# SCH_Ribery_MotherBoard_2024-03-02.net
KiCad netlist of a schematic drawn in EasyEDA
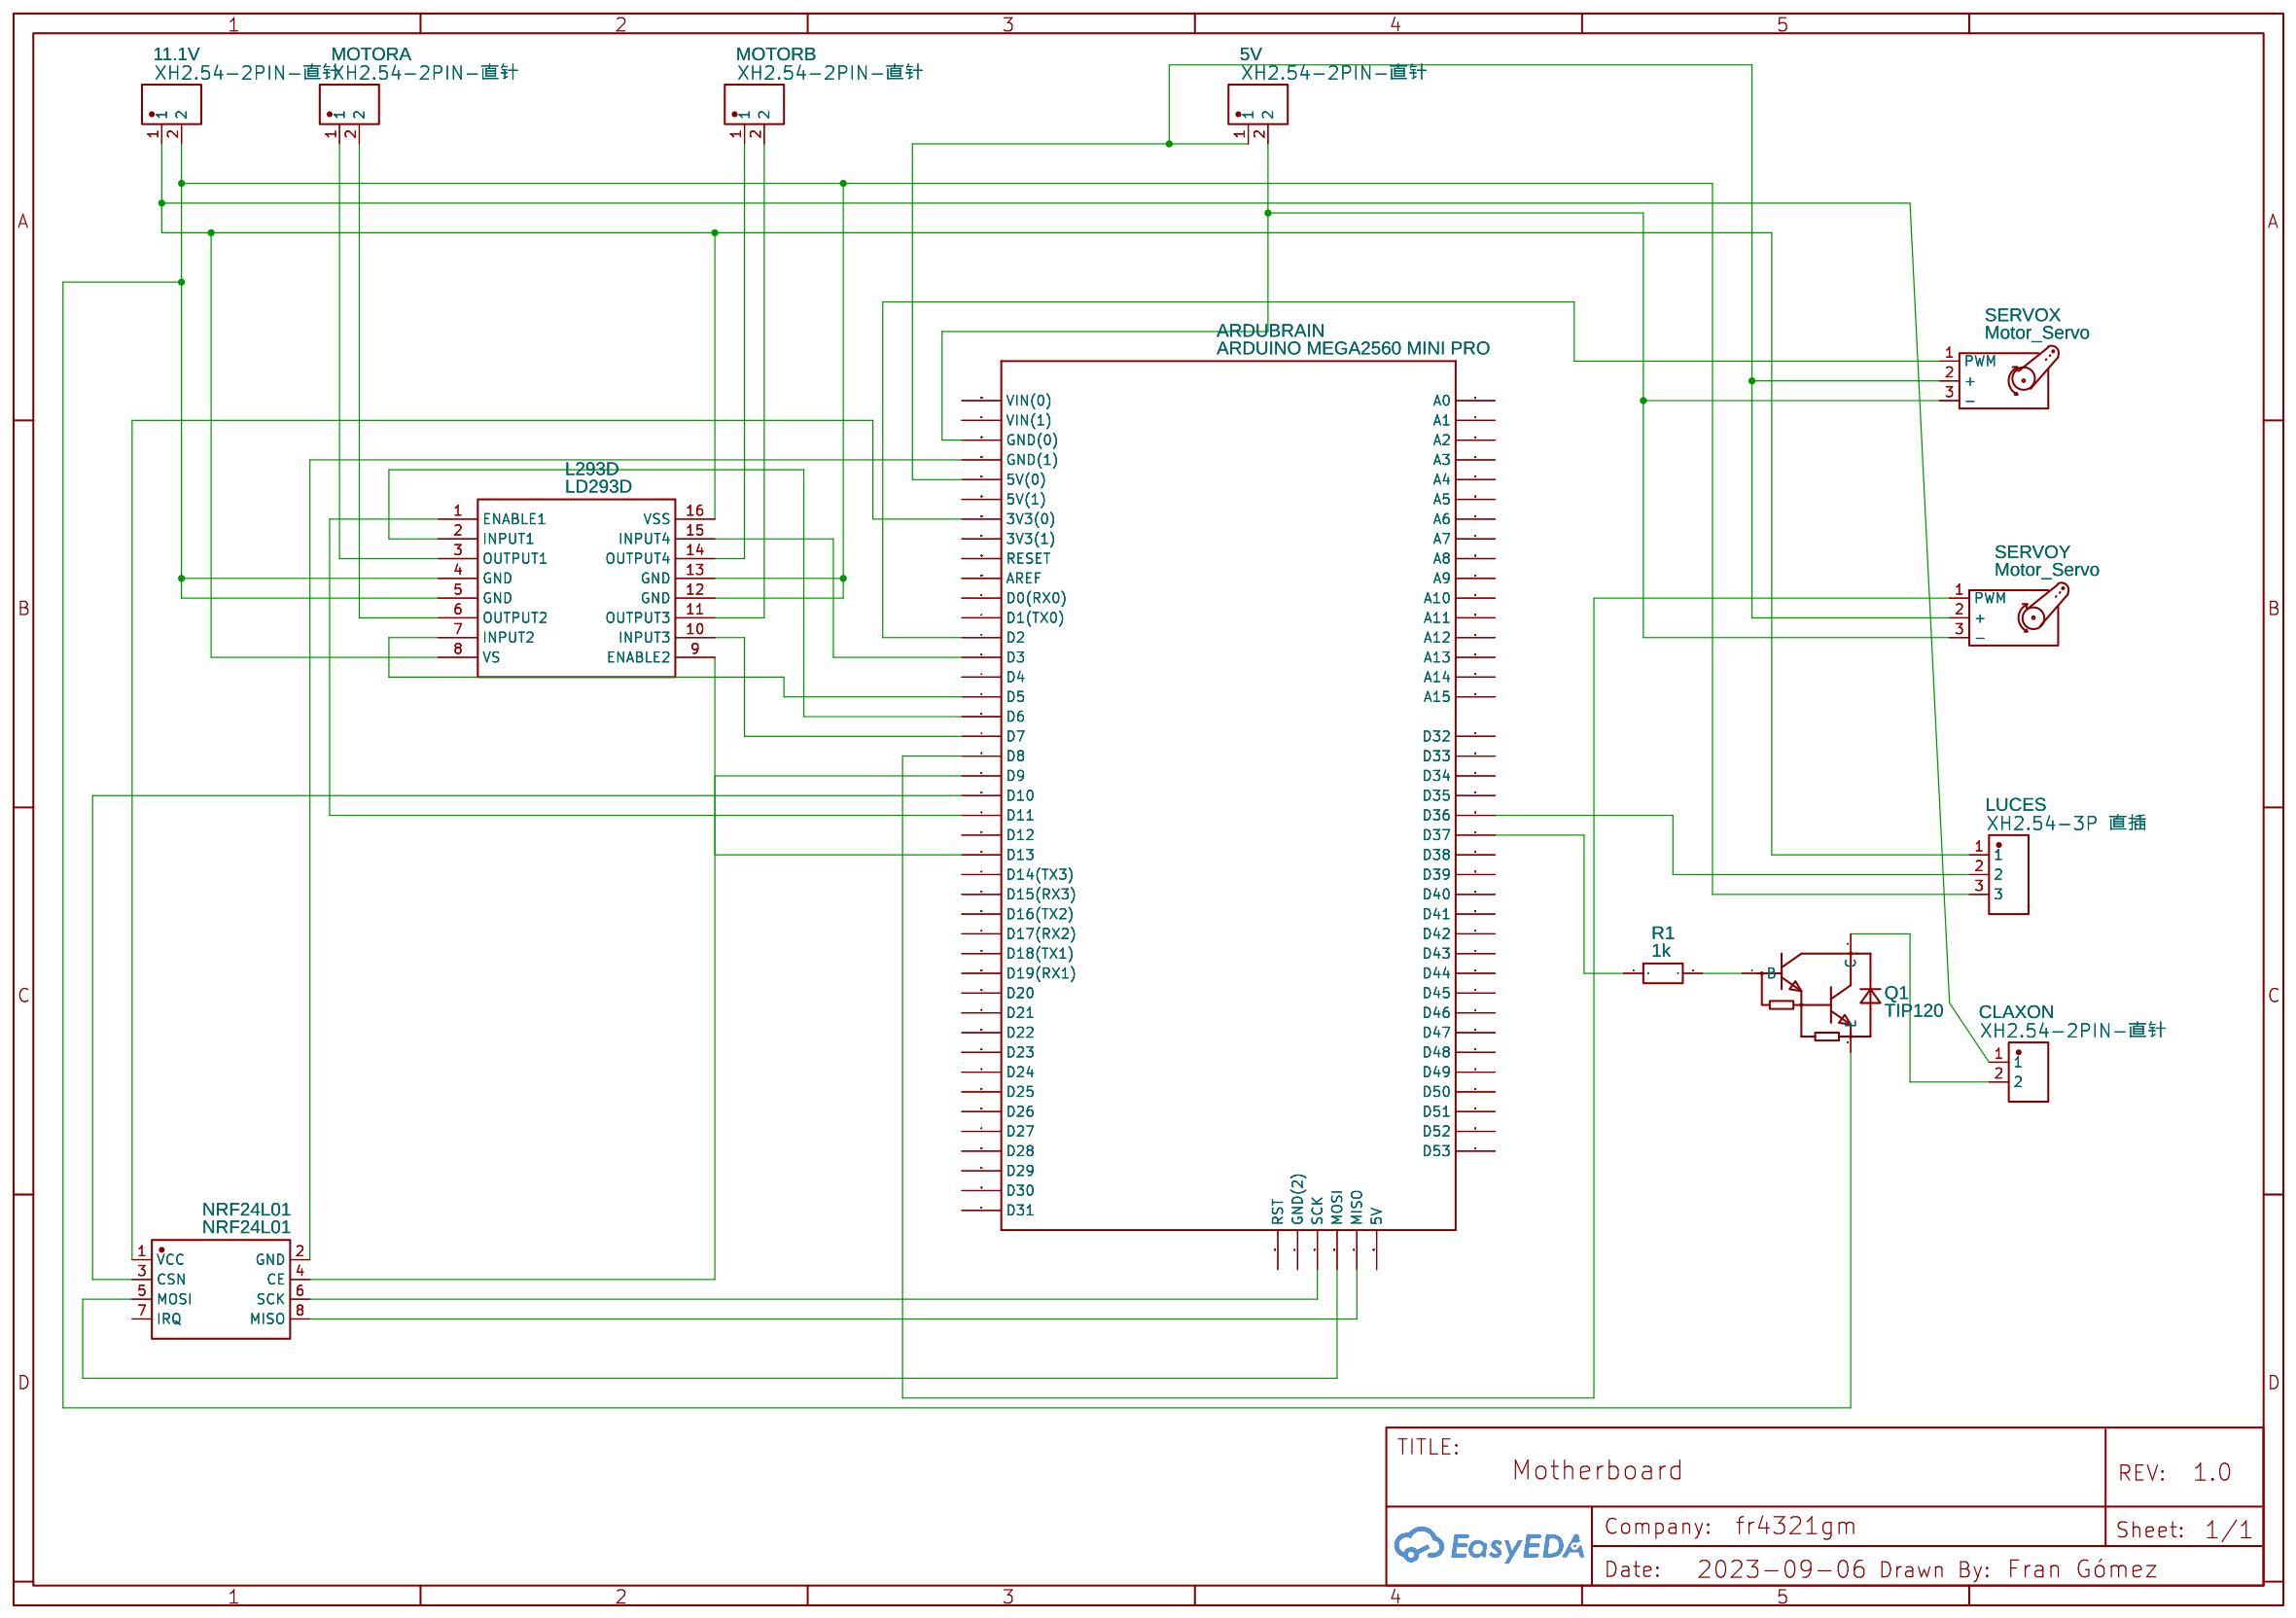
[diagram p0: schematic sheet]

(export (version "E")
  (design (tool "Eeschema 10.0.6"))
  (components
    (comp (ref "5V") (value "XH2.54-2PIN-直针") (libsource (lib "") (part "XH2.54-2PIN-直针_4")))
    (comp (ref "11.1V") (value "XH2.54-2PIN-直针") (libsource (lib "") (part "XH2.54-2PIN-直针_3")))
    (comp (ref "ARDUBRAIN")
      (value "ARDUINO MEGA2560 MINI PRO")
      (libsource (lib "") (part "ARDUINO MEGA2560 MINI PRO"))
    )
    (comp (ref "CLAXON") (value "XH2.54-2PIN-直针") (libsource (lib "") (part "XH2.54-2PIN-直针_2")))
    (comp (ref "L293D")
      (value "LD293D")
      (fields (field (name "Manufacturer Part") "L293D") (field (name "Manufacturer") "STMicroelectronics"))
      (libsource (lib "") (part "LD293D///2"))
    )
    (comp (ref "LUCES") (value "XH2.54-3P 直插") (libsource (lib "") (part "XH2.54-3P 直插")))
    (comp (ref "MOTORA") (value "XH2.54-2PIN-直针") (libsource (lib "") (part "XH2.54-2PIN-直针")))
    (comp (ref "MOTORB") (value "XH2.54-2PIN-直针") (libsource (lib "") (part "XH2.54-2PIN-直针_1")))
    (comp (ref "NRF24L01")
      (value "NRF24L01")
      (fields (field (name "Manufacturer Part") "NF-04") (field (name "Manufacturer") "Ai-Thinker(安信可)"))
      (libsource (lib "") (part "NRF24L01"))
    )
    (comp (ref "Q1")
      (value "TIP120")
      (fields (field (name "Manufacturer") "ST(意法半导体)"))
      (libsource (lib "") (part "TIP120"))
    )
    (comp (ref "R1") (value "1k") (libsource (lib "") (part "R_AXIAL-0.3_EU")))
    (comp (ref "SERVOX") (value "Motor_Servo") (libsource (lib "") (part "Motor_Servo_1")))
    (comp (ref "SERVOY") (value "Motor_Servo") (libsource (lib "") (part "Motor_Servo")))
  )
  (nets
    (net (code "1") (name "Net-(ARDUBRAIN-3V3(0))") (class "Default")
      (node (ref "ARDUBRAIN") (pin "106") (pinfunction "3V3(0)_106") (pintype "unspecified"))
      (node (ref "NRF24L01") (pin "1") (pinfunction "VCC_1") (pintype "unspecified"))
    )
    (net (code "2") (name "Net-(ARDUBRAIN-5V(0))") (class "Default")
      (node (ref "5V") (pin "1") (pinfunction "1_1") (pintype "unspecified"))
      (node (ref "ARDUBRAIN") (pin "104") (pinfunction "5V(0)_104") (pintype "unspecified"))
      (node (ref "SERVOX") (pin "2") (pinfunction "+_2") (pintype "unspecified"))
      (node (ref "SERVOY") (pin "2") (pinfunction "+_2") (pintype "unspecified"))
    )
    (net (code "3") (name "Net-(ARDUBRAIN-D2)") (class "Default")
      (node (ref "ARDUBRAIN") (pin "2") (pinfunction "D2_2") (pintype "unspecified"))
      (node (ref "SERVOX") (pin "1") (pinfunction "PWM_1") (pintype "unspecified"))
    )
    (net (code "4") (name "Net-(ARDUBRAIN-D3)") (class "Default")
      (node (ref "ARDUBRAIN") (pin "3") (pinfunction "D3_3") (pintype "unspecified"))
      (node (ref "L293D") (pin "15") (pinfunction "INPUT4_15") (pintype "unspecified"))
    )
    (net (code "5") (name "Net-(ARDUBRAIN-D5)") (class "Default")
      (node (ref "ARDUBRAIN") (pin "5") (pinfunction "D5_5") (pintype "unspecified"))
      (node (ref "L293D") (pin "7") (pinfunction "INPUT2_7") (pintype "unspecified"))
    )
    (net (code "6") (name "Net-(ARDUBRAIN-D6)") (class "Default")
      (node (ref "ARDUBRAIN") (pin "6") (pinfunction "D6_6") (pintype "unspecified"))
      (node (ref "L293D") (pin "2") (pinfunction "INPUT1_2") (pintype "unspecified"))
    )
    (net (code "7") (name "Net-(ARDUBRAIN-D7)") (class "Default")
      (node (ref "ARDUBRAIN") (pin "7") (pinfunction "D7_7") (pintype "unspecified"))
      (node (ref "L293D") (pin "10") (pinfunction "INPUT3_10") (pintype "unspecified"))
    )
    (net (code "8") (name "Net-(ARDUBRAIN-D8)") (class "Default")
      (node (ref "ARDUBRAIN") (pin "8") (pinfunction "D8_8") (pintype "unspecified"))
      (node (ref "SERVOY") (pin "1") (pinfunction "PWM_1") (pintype "unspecified"))
    )
    (net (code "9") (name "Net-(ARDUBRAIN-D9)") (class "Default")
      (node (ref "ARDUBRAIN") (pin "9") (pinfunction "D9_9") (pintype "unspecified"))
      (node (ref "NRF24L01") (pin "4") (pinfunction "CE_4") (pintype "unspecified"))
    )
    (net (code "10") (name "Net-(ARDUBRAIN-D10)") (class "Default")
      (node (ref "ARDUBRAIN") (pin "10") (pinfunction "D10_10") (pintype "unspecified"))
      (node (ref "NRF24L01") (pin "3") (pinfunction "CSN_3") (pintype "unspecified"))
    )
    (net (code "11") (name "Net-(ARDUBRAIN-D11)") (class "Default")
      (node (ref "ARDUBRAIN") (pin "11") (pinfunction "D11_11") (pintype "unspecified"))
      (node (ref "L293D") (pin "1") (pinfunction "ENABLE1_1") (pintype "unspecified"))
    )
    (net (code "12") (name "Net-(ARDUBRAIN-D13)") (class "Default")
      (node (ref "ARDUBRAIN") (pin "13") (pinfunction "D13_13") (pintype "unspecified"))
      (node (ref "L293D") (pin "9") (pinfunction "ENABLE2_9") (pintype "unspecified"))
    )
    (net (code "13") (name "Net-(ARDUBRAIN-D36)") (class "Default")
      (node (ref "ARDUBRAIN") (pin "36") (pinfunction "D36_36") (pintype "unspecified"))
      (node (ref "LUCES") (pin "2") (pinfunction "2_2") (pintype "unspecified"))
    )
    (net (code "14") (name "Net-(ARDUBRAIN-D37)") (class "Default")
      (node (ref "ARDUBRAIN") (pin "37") (pinfunction "D37_37") (pintype "unspecified"))
      (node (ref "R1") (pin "1") (pinfunction "1_1") (pintype "unspecified"))
    )
    (net (code "15") (name "Net-(ARDUBRAIN-GND(0))") (class "Default")
      (node (ref "5V") (pin "2") (pinfunction "2_2") (pintype "unspecified"))
      (node (ref "ARDUBRAIN") (pin "102") (pinfunction "GND(0)_102") (pintype "unspecified"))
      (node (ref "SERVOX") (pin "3") (pinfunction "-_3") (pintype "unspecified"))
      (node (ref "SERVOY") (pin "3") (pinfunction "-_3") (pintype "unspecified"))
    )
    (net (code "16") (name "Net-(ARDUBRAIN-GND(1))") (class "Default")
      (node (ref "ARDUBRAIN") (pin "103") (pinfunction "GND(1)_103") (pintype "unspecified"))
      (node (ref "NRF24L01") (pin "2") (pinfunction "GND_2") (pintype "unspecified"))
    )
    (net (code "17") (name "Net-(ARDUBRAIN-MISO)") (class "Default")
      (node (ref "ARDUBRAIN") (pin "111") (pinfunction "MISO_111") (pintype "unspecified"))
      (node (ref "NRF24L01") (pin "8") (pinfunction "MISO_8") (pintype "unspecified"))
    )
    (net (code "18") (name "Net-(ARDUBRAIN-MOSI)") (class "Default")
      (node (ref "ARDUBRAIN") (pin "112") (pinfunction "MOSI_112") (pintype "unspecified"))
      (node (ref "NRF24L01") (pin "5") (pinfunction "MOSI_5") (pintype "unspecified"))
    )
    (net (code "19") (name "Net-(ARDUBRAIN-SCK)") (class "Default")
      (node (ref "ARDUBRAIN") (pin "113") (pinfunction "SCK_113") (pintype "unspecified"))
      (node (ref "NRF24L01") (pin "6") (pinfunction "SCK_6") (pintype "unspecified"))
    )
    (net (code "20") (name "Net-(L293D-OUTPUT1)") (class "Default")
      (node (ref "L293D") (pin "3") (pinfunction "OUTPUT1_3") (pintype "unspecified"))
      (node (ref "MOTORA") (pin "1") (pinfunction "1_1") (pintype "unspecified"))
    )
    (net (code "21") (name "Net-(L293D-OUTPUT2)") (class "Default")
      (node (ref "L293D") (pin "6") (pinfunction "OUTPUT2_6") (pintype "unspecified"))
      (node (ref "MOTORA") (pin "2") (pinfunction "2_2") (pintype "unspecified"))
    )
    (net (code "22") (name "Net-(L293D-OUTPUT3)") (class "Default")
      (node (ref "L293D") (pin "11") (pinfunction "OUTPUT3_11") (pintype "unspecified"))
      (node (ref "MOTORB") (pin "2") (pinfunction "2_2") (pintype "unspecified"))
    )
    (net (code "23") (name "Net-(L293D-OUTPUT4)") (class "Default")
      (node (ref "L293D") (pin "14") (pinfunction "OUTPUT4_14") (pintype "unspecified"))
      (node (ref "MOTORB") (pin "1") (pinfunction "1_1") (pintype "unspecified"))
    )
    (net (code "24") (name "Net-(L293D-VS)") (class "Default")
      (node (ref "11.1V") (pin "1") (pinfunction "1_1") (pintype "unspecified"))
      (node (ref "CLAXON") (pin "1") (pinfunction "1_1") (pintype "unspecified"))
      (node (ref "L293D") (pin "16") (pinfunction "VSS_16") (pintype "unspecified"))
      (node (ref "L293D") (pin "8") (pinfunction "VS_8") (pintype "unspecified"))
      (node (ref "LUCES") (pin "1") (pinfunction "1_1") (pintype "unspecified"))
    )
    (net (code "25") (name "Net-(Q1-B)") (class "Default")
      (node (ref "Q1") (pin "1") (pinfunction "B_1") (pintype "input"))
      (node (ref "R1") (pin "2") (pinfunction "2_2") (pintype "unspecified"))
    )
    (net (code "26") (name "Net-(Q1-C)") (class "Default")
      (node (ref "CLAXON") (pin "2") (pinfunction "2_2") (pintype "unspecified"))
      (node (ref "Q1") (pin "2") (pinfunction "C_2") (pintype "input"))
    )
    (net (code "27") (name "Net-(Q1-E)") (class "Default")
      (node (ref "11.1V") (pin "2") (pinfunction "2_2") (pintype "unspecified"))
      (node (ref "L293D") (pin "12") (pinfunction "GND_12") (pintype "unspecified"))
      (node (ref "L293D") (pin "13") (pinfunction "GND_13") (pintype "unspecified"))
      (node (ref "L293D") (pin "4") (pinfunction "GND_4") (pintype "unspecified"))
      (node (ref "L293D") (pin "5") (pinfunction "GND_5") (pintype "unspecified"))
      (node (ref "LUCES") (pin "3") (pinfunction "3_3") (pintype "unspecified"))
      (node (ref "Q1") (pin "3") (pinfunction "E_3") (pintype "input"))
    )
    (net (code "28") (name "unconnected-(ARDUBRAIN-3V3(1)-Pad107)") (class "Default")
      (node (ref "ARDUBRAIN") (pin "107") (pinfunction "3V3(1)_107") (pintype "unspecified"))
    )
    (net (code "29") (name "unconnected-(ARDUBRAIN-5V(1)-Pad105)") (class "Default")
      (node (ref "ARDUBRAIN") (pin "105") (pinfunction "5V(1)_105") (pintype "unspecified"))
    )
    (net (code "30") (name "unconnected-(ARDUBRAIN-5V-Pad110)") (class "Default")
      (node (ref "ARDUBRAIN") (pin "110") (pinfunction "5V_110") (pintype "unspecified"))
    )
    (net (code "31") (name "unconnected-(ARDUBRAIN-A0-Pad54)") (class "Default")
      (node (ref "ARDUBRAIN") (pin "54") (pinfunction "A0_54") (pintype "unspecified"))
    )
    (net (code "32") (name "unconnected-(ARDUBRAIN-A1-Pad55)") (class "Default")
      (node (ref "ARDUBRAIN") (pin "55") (pinfunction "A1_55") (pintype "unspecified"))
    )
    (net (code "33") (name "unconnected-(ARDUBRAIN-A2-Pad56)") (class "Default")
      (node (ref "ARDUBRAIN") (pin "56") (pinfunction "A2_56") (pintype "unspecified"))
    )
    (net (code "34") (name "unconnected-(ARDUBRAIN-A3-Pad57)") (class "Default")
      (node (ref "ARDUBRAIN") (pin "57") (pinfunction "A3_57") (pintype "unspecified"))
    )
    (net (code "35") (name "unconnected-(ARDUBRAIN-A4-Pad58)") (class "Default")
      (node (ref "ARDUBRAIN") (pin "58") (pinfunction "A4_58") (pintype "unspecified"))
    )
    (net (code "36") (name "unconnected-(ARDUBRAIN-A5-Pad59)") (class "Default")
      (node (ref "ARDUBRAIN") (pin "59") (pinfunction "A5_59") (pintype "unspecified"))
    )
    (net (code "37") (name "unconnected-(ARDUBRAIN-A6-Pad60)") (class "Default")
      (node (ref "ARDUBRAIN") (pin "60") (pinfunction "A6_60") (pintype "unspecified"))
    )
    (net (code "38") (name "unconnected-(ARDUBRAIN-A7-Pad61)") (class "Default")
      (node (ref "ARDUBRAIN") (pin "61") (pinfunction "A7_61") (pintype "unspecified"))
    )
    (net (code "39") (name "unconnected-(ARDUBRAIN-A8-Pad62)") (class "Default")
      (node (ref "ARDUBRAIN") (pin "62") (pinfunction "A8_62") (pintype "unspecified"))
    )
    (net (code "40") (name "unconnected-(ARDUBRAIN-A9-Pad63)") (class "Default")
      (node (ref "ARDUBRAIN") (pin "63") (pinfunction "A9_63") (pintype "unspecified"))
    )
    (net (code "41") (name "unconnected-(ARDUBRAIN-A10-Pad64)") (class "Default")
      (node (ref "ARDUBRAIN") (pin "64") (pinfunction "A10_64") (pintype "unspecified"))
    )
    (net (code "42") (name "unconnected-(ARDUBRAIN-A11-Pad65)") (class "Default")
      (node (ref "ARDUBRAIN") (pin "65") (pinfunction "A11_65") (pintype "unspecified"))
    )
    (net (code "43") (name "unconnected-(ARDUBRAIN-A12-Pad66)") (class "Default")
      (node (ref "ARDUBRAIN") (pin "66") (pinfunction "A12_66") (pintype "unspecified"))
    )
    (net (code "44") (name "unconnected-(ARDUBRAIN-A13-Pad67)") (class "Default")
      (node (ref "ARDUBRAIN") (pin "67") (pinfunction "A13_67") (pintype "unspecified"))
    )
    (net (code "45") (name "unconnected-(ARDUBRAIN-A14-Pad68)") (class "Default")
      (node (ref "ARDUBRAIN") (pin "68") (pinfunction "A14_68") (pintype "unspecified"))
    )
    (net (code "46") (name "unconnected-(ARDUBRAIN-A15-Pad69)") (class "Default")
      (node (ref "ARDUBRAIN") (pin "69") (pinfunction "A15_69") (pintype "unspecified"))
    )
    (net (code "47") (name "unconnected-(ARDUBRAIN-AREF-Pad109)") (class "Default")
      (node (ref "ARDUBRAIN") (pin "109") (pinfunction "AREF_109") (pintype "unspecified"))
    )
    (net (code "48") (name "unconnected-(ARDUBRAIN-D0(RX0)-Pad0)") (class "Default")
      (node (ref "ARDUBRAIN") (pin "0") (pinfunction "D0(RX0)_0") (pintype "unspecified"))
    )
    (net (code "49") (name "unconnected-(ARDUBRAIN-D1(TX0)-Pad1)") (class "Default")
      (node (ref "ARDUBRAIN") (pin "1") (pinfunction "D1(TX0)_1") (pintype "unspecified"))
    )
    (net (code "50") (name "unconnected-(ARDUBRAIN-D4-Pad4)") (class "Default")
      (node (ref "ARDUBRAIN") (pin "4") (pinfunction "D4_4") (pintype "unspecified"))
    )
    (net (code "51") (name "unconnected-(ARDUBRAIN-D12-Pad12)") (class "Default")
      (node (ref "ARDUBRAIN") (pin "12") (pinfunction "D12_12") (pintype "unspecified"))
    )
    (net (code "52") (name "unconnected-(ARDUBRAIN-D14(TX3)-Pad14)") (class "Default")
      (node (ref "ARDUBRAIN") (pin "14") (pinfunction "D14(TX3)_14") (pintype "unspecified"))
    )
    (net (code "53") (name "unconnected-(ARDUBRAIN-D15(RX3)-Pad15)") (class "Default")
      (node (ref "ARDUBRAIN") (pin "15") (pinfunction "D15(RX3)_15") (pintype "unspecified"))
    )
    (net (code "54") (name "unconnected-(ARDUBRAIN-D16(TX2)-Pad16)") (class "Default")
      (node (ref "ARDUBRAIN") (pin "16") (pinfunction "D16(TX2)_16") (pintype "unspecified"))
    )
    (net (code "55") (name "unconnected-(ARDUBRAIN-D17(RX2)-Pad17)") (class "Default")
      (node (ref "ARDUBRAIN") (pin "17") (pinfunction "D17(RX2)_17") (pintype "unspecified"))
    )
    (net (code "56") (name "unconnected-(ARDUBRAIN-D18(TX1)-Pad18)") (class "Default")
      (node (ref "ARDUBRAIN") (pin "18") (pinfunction "D18(TX1)_18") (pintype "unspecified"))
    )
    (net (code "57") (name "unconnected-(ARDUBRAIN-D19(RX1)-Pad19)") (class "Default")
      (node (ref "ARDUBRAIN") (pin "19") (pinfunction "D19(RX1)_19") (pintype "unspecified"))
    )
    (net (code "58") (name "unconnected-(ARDUBRAIN-D20-Pad20)") (class "Default")
      (node (ref "ARDUBRAIN") (pin "20") (pinfunction "D20_20") (pintype "unspecified"))
    )
    (net (code "59") (name "unconnected-(ARDUBRAIN-D21-Pad21)") (class "Default")
      (node (ref "ARDUBRAIN") (pin "21") (pinfunction "D21_21") (pintype "unspecified"))
    )
    (net (code "60") (name "unconnected-(ARDUBRAIN-D22-Pad22)") (class "Default")
      (node (ref "ARDUBRAIN") (pin "22") (pinfunction "D22_22") (pintype "unspecified"))
    )
    (net (code "61") (name "unconnected-(ARDUBRAIN-D23-Pad23)") (class "Default")
      (node (ref "ARDUBRAIN") (pin "23") (pinfunction "D23_23") (pintype "unspecified"))
    )
    (net (code "62") (name "unconnected-(ARDUBRAIN-D24-Pad24)") (class "Default")
      (node (ref "ARDUBRAIN") (pin "24") (pinfunction "D24_24") (pintype "unspecified"))
    )
    (net (code "63") (name "unconnected-(ARDUBRAIN-D25-Pad25)") (class "Default")
      (node (ref "ARDUBRAIN") (pin "25") (pinfunction "D25_25") (pintype "unspecified"))
    )
    (net (code "64") (name "unconnected-(ARDUBRAIN-D26-Pad26)") (class "Default")
      (node (ref "ARDUBRAIN") (pin "26") (pinfunction "D26_26") (pintype "unspecified"))
    )
    (net (code "65") (name "unconnected-(ARDUBRAIN-D27-Pad27)") (class "Default")
      (node (ref "ARDUBRAIN") (pin "27") (pinfunction "D27_27") (pintype "unspecified"))
    )
    (net (code "66") (name "unconnected-(ARDUBRAIN-D28-Pad28)") (class "Default")
      (node (ref "ARDUBRAIN") (pin "28") (pinfunction "D28_28") (pintype "unspecified"))
    )
    (net (code "67") (name "unconnected-(ARDUBRAIN-D29-Pad29)") (class "Default")
      (node (ref "ARDUBRAIN") (pin "29") (pinfunction "D29_29") (pintype "unspecified"))
    )
    (net (code "68") (name "unconnected-(ARDUBRAIN-D30-Pad30)") (class "Default")
      (node (ref "ARDUBRAIN") (pin "30") (pinfunction "D30_30") (pintype "unspecified"))
    )
    (net (code "69") (name "unconnected-(ARDUBRAIN-D31-Pad31)") (class "Default")
      (node (ref "ARDUBRAIN") (pin "31") (pinfunction "D31_31") (pintype "unspecified"))
    )
    (net (code "70") (name "unconnected-(ARDUBRAIN-D32-Pad32)") (class "Default")
      (node (ref "ARDUBRAIN") (pin "32") (pinfunction "D32_32") (pintype "unspecified"))
    )
    (net (code "71") (name "unconnected-(ARDUBRAIN-D33-Pad33)") (class "Default")
      (node (ref "ARDUBRAIN") (pin "33") (pinfunction "D33_33") (pintype "unspecified"))
    )
    (net (code "72") (name "unconnected-(ARDUBRAIN-D34-Pad34)") (class "Default")
      (node (ref "ARDUBRAIN") (pin "34") (pinfunction "D34_34") (pintype "unspecified"))
    )
    (net (code "73") (name "unconnected-(ARDUBRAIN-D35-Pad35)") (class "Default")
      (node (ref "ARDUBRAIN") (pin "35") (pinfunction "D35_35") (pintype "unspecified"))
    )
    (net (code "74") (name "unconnected-(ARDUBRAIN-D38-Pad38)") (class "Default")
      (node (ref "ARDUBRAIN") (pin "38") (pinfunction "D38_38") (pintype "unspecified"))
    )
    (net (code "75") (name "unconnected-(ARDUBRAIN-D39-Pad39)") (class "Default")
      (node (ref "ARDUBRAIN") (pin "39") (pinfunction "D39_39") (pintype "unspecified"))
    )
    (net (code "76") (name "unconnected-(ARDUBRAIN-D40-Pad40)") (class "Default")
      (node (ref "ARDUBRAIN") (pin "40") (pinfunction "D40_40") (pintype "unspecified"))
    )
    (net (code "77") (name "unconnected-(ARDUBRAIN-D41-Pad41)") (class "Default")
      (node (ref "ARDUBRAIN") (pin "41") (pinfunction "D41_41") (pintype "unspecified"))
    )
    (net (code "78") (name "unconnected-(ARDUBRAIN-D42-Pad42)") (class "Default")
      (node (ref "ARDUBRAIN") (pin "42") (pinfunction "D42_42") (pintype "unspecified"))
    )
    (net (code "79") (name "unconnected-(ARDUBRAIN-D43-Pad43)") (class "Default")
      (node (ref "ARDUBRAIN") (pin "43") (pinfunction "D43_43") (pintype "unspecified"))
    )
    (net (code "80") (name "unconnected-(ARDUBRAIN-D44-Pad44)") (class "Default")
      (node (ref "ARDUBRAIN") (pin "44") (pinfunction "D44_44") (pintype "unspecified"))
    )
    (net (code "81") (name "unconnected-(ARDUBRAIN-D45-Pad45)") (class "Default")
      (node (ref "ARDUBRAIN") (pin "45") (pinfunction "D45_45") (pintype "unspecified"))
    )
    (net (code "82") (name "unconnected-(ARDUBRAIN-D46-Pad46)") (class "Default")
      (node (ref "ARDUBRAIN") (pin "46") (pinfunction "D46_46") (pintype "unspecified"))
    )
    (net (code "83") (name "unconnected-(ARDUBRAIN-D47-Pad47)") (class "Default")
      (node (ref "ARDUBRAIN") (pin "47") (pinfunction "D47_47") (pintype "unspecified"))
    )
    (net (code "84") (name "unconnected-(ARDUBRAIN-D48-Pad48)") (class "Default")
      (node (ref "ARDUBRAIN") (pin "48") (pinfunction "D48_48") (pintype "unspecified"))
    )
    (net (code "85") (name "unconnected-(ARDUBRAIN-D49-Pad49)") (class "Default")
      (node (ref "ARDUBRAIN") (pin "49") (pinfunction "D49_49") (pintype "unspecified"))
    )
    (net (code "86") (name "unconnected-(ARDUBRAIN-D50-Pad50)") (class "Default")
      (node (ref "ARDUBRAIN") (pin "50") (pinfunction "D50_50") (pintype "unspecified"))
    )
    (net (code "87") (name "unconnected-(ARDUBRAIN-D51-Pad51)") (class "Default")
      (node (ref "ARDUBRAIN") (pin "51") (pinfunction "D51_51") (pintype "unspecified"))
    )
    (net (code "88") (name "unconnected-(ARDUBRAIN-D52-Pad52)") (class "Default")
      (node (ref "ARDUBRAIN") (pin "52") (pinfunction "D52_52") (pintype "unspecified"))
    )
    (net (code "89") (name "unconnected-(ARDUBRAIN-D53-Pad53)") (class "Default")
      (node (ref "ARDUBRAIN") (pin "53") (pinfunction "D53_53") (pintype "unspecified"))
    )
    (net (code "90") (name "unconnected-(ARDUBRAIN-GND(2)-Pad114)") (class "Default")
      (node (ref "ARDUBRAIN") (pin "114") (pinfunction "GND(2)_114") (pintype "unspecified"))
    )
    (net (code "91") (name "unconnected-(ARDUBRAIN-RESET-Pad108)") (class "Default")
      (node (ref "ARDUBRAIN") (pin "108") (pinfunction "RESET_108") (pintype "unspecified"))
    )
    (net (code "92") (name "unconnected-(ARDUBRAIN-RST-Pad115)") (class "Default")
      (node (ref "ARDUBRAIN") (pin "115") (pinfunction "RST_115") (pintype "unspecified"))
    )
    (net (code "93") (name "unconnected-(ARDUBRAIN-VIN(0)-Pad100)") (class "Default")
      (node (ref "ARDUBRAIN") (pin "100") (pinfunction "VIN(0)_100") (pintype "unspecified"))
    )
    (net (code "94") (name "unconnected-(ARDUBRAIN-VIN(1)-Pad101)") (class "Default")
      (node (ref "ARDUBRAIN") (pin "101") (pinfunction "VIN(1)_101") (pintype "unspecified"))
    )
    (net (code "95") (name "unconnected-(NRF24L01-IRQ-Pad7)") (class "Default")
      (node (ref "NRF24L01") (pin "7") (pinfunction "IRQ_7") (pintype "unspecified"))
    )
  )
)
